# High-Speed_Interfaces.net
KiCad netlist of a schematic drawn in Altium Designer
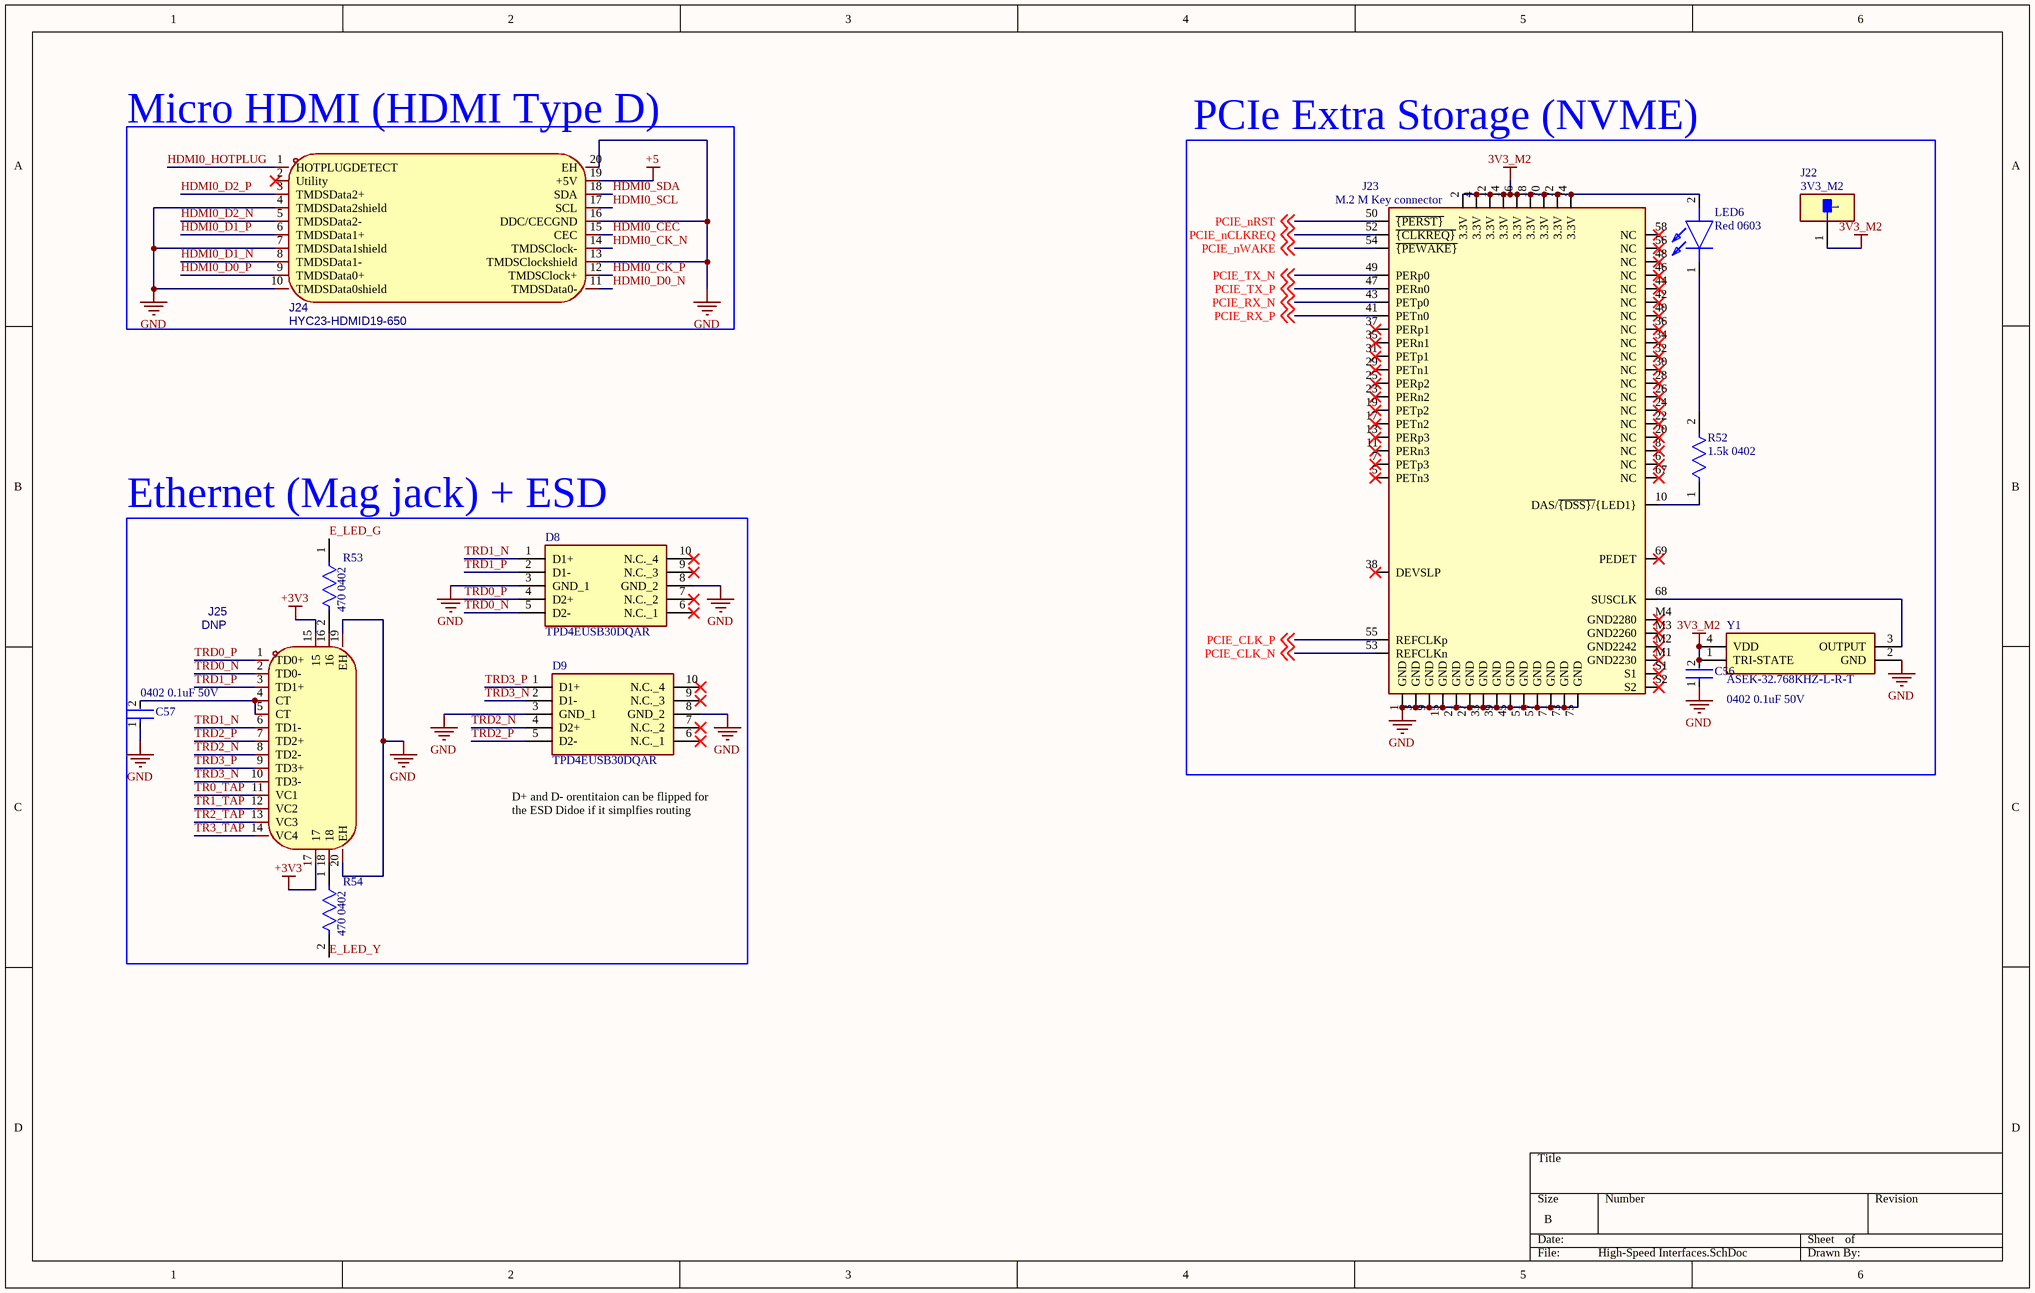
[diagram p0: High-Speed Interfaces.SchDoc]

(export (version "E")
  (design (tool "Eeschema 10.0.6"))
  (components
    (comp (ref "C56")
      (value "0402 0.1uF 50V")
      (footprint "FP-C0402-BB-MFG")
      (description "C307331")
      (fields
        (field (name "TOLERANCE") "0.2")
        (field (name "OCTOPART") "https://octopart.com/c0402c104m3pac7867-kemet-84304880")
      )
      (libsource (lib "Altium Content Vault") (part "b4654b650e69147ec39a6b967a45e02"))
    )
    (comp (ref "C57")
      (value "0402 0.1uF 50V")
      (footprint "FP-C0402-BB-MFG")
      (description "C307331")
      (fields
        (field (name "TOLERANCE") "0.2")
        (field (name "OCTOPART") "https://octopart.com/c0402c104m3pac7867-kemet-84304880")
      )
      (libsource (lib "Altium Content Vault") (part "b4654b650e69147ec39a6b967a45e02"))
    )
    (comp (ref "D8")
      (value "TPD4EUSB30DQAR")
      (footprint "SamacSys:DQA(R-PUSON-N10)")
      (description "C90627")
      (fields (field (name "MOUSER PART NUMBER") "595-TPD4EUSB30DQAR"))
      (libsource (lib "*") (part "TPD4EUSB30DQAR"))
    )
    (comp (ref "D9")
      (value "TPD4EUSB30DQAR")
      (footprint "SamacSys:DQA(R-PUSON-N10)")
      (description "C90627")
      (fields (field (name "MOUSER PART NUMBER") "595-TPD4EUSB30DQAR"))
      (libsource (lib "*") (part "TPD4EUSB30DQAR"))
    )
    (comp (ref "J22")
      (value "3V3_M2")
      (footprint "FP-5015-MFG")
      (description "PC TEST POINT MINIATURE")
      (fields (field (name "MANUFACTURER PART NUMBER") "5015") (field (name "MANUFACTURER") "keystone"))
      (libsource (lib "Altium Content Vault") (part "dd45045ce8184df9e99e12baf3f412c"))
    )
    (comp (ref "J23")
      (value "M.2 M Key connector")
      (footprint "M.2 M Key connector RPI")
      (description "C841661")
      (libsource (lib "Schlib1") (part "M.2 M Key connector RPI"))
    )
    (comp (ref "J24")
      (value "HYC23-HDMID19-650")
      (footprint "AUDIO-TH_HYC23-HDMID19-650")
      (description "C711358")
      (fields (field (name "MANUFACTURER") "华宇创"))
      (libsource (lib "Schlib1") (part "HDMI"))
    )
    (comp (ref "J25")
      (value "DNP")
      (footprint "RJ45-TH_LPJG0926HENL_C22457393")
      (description "C22457393")
      (fields (field (name "MANUFACTURER") "LINK-PP(连普科技)") (field (name "MANUFACTURER PART") "LPJG0926HENL"))
      (libsource (lib "Schlib1") (part "Ethernet Correct"))
    )
    (comp (ref "LED6")
      (value "Red 0603")
      (footprint "SamacSys:LEDC1608X70N")
      (description "C2286")
      (fields (field (name "MANUFACTURER_PART_NUMBER") "KT-0603R"))
      (libsource (lib "*") (part "KT-0603R"))
    )
    (comp (ref "R52")
      (value "1.5k 0402")
      (footprint "FP-AF0402-IPC_B")
      (description "C25867")
      (fields (field (name "TOLERANCE") "5%"))
      (libsource (lib "Altium Content Vault") (part "1029c3af85768c4190bb7ad29bc67b5"))
    )
    (comp (ref "R53")
      (value "470 0402")
      (footprint "FP-RMCF0402-MFG")
      (description "C25117")
      (fields (field (name "TOLERANCE") "5%"))
      (libsource (lib "Altium Content Vault") (part "1029c3af85768c4190bb7ad29bc67b5"))
    )
    (comp (ref "R54")
      (value "470 0402")
      (footprint "FP-RMCF0402-MFG")
      (description "C25117")
      (fields (field (name "TOLERANCE") "5%"))
      (libsource (lib "Altium Content Vault") (part "1029c3af85768c4190bb7ad29bc67b5"))
    )
    (comp (ref "Y1")
      (value "ASEK-32.768KHZ-L-R-T")
      (footprint "SamacSys:ASEK32768KHZLRT")
      (description "C2650753")
      (libsource (lib "*") (part "ASEK-32.768KHZ-L-R-T"))
    )
  )
  (nets
    (net (code "1") (name "+3V3") (class "Default")
      (node (ref "J25") (pin "15") (pinfunction "15_15") (pintype "passive"))
      (node (ref "J25") (pin "17") (pinfunction "17_17") (pintype "passive"))
    )
    (net (code "2") (name "+5") (class "Default")
      (node (ref "J24") (pin "19") (pinfunction "+5V_19") (pintype "passive"))
    )
    (net (code "3") (name "/E_LED_G") (class "Default")
      (node (ref "R53") (pin "1") (pinfunction "1_1") (pintype "passive"))
    )
    (net (code "4") (name "/E_LED_Y") (class "Default")
      (node (ref "R54") (pin "2") (pinfunction "2_2") (pintype "passive"))
    )
    (net (code "5") (name "/HDMI0_CEC") (class "Default")
      (node (ref "J24") (pin "15") (pinfunction "CEC_15") (pintype "passive"))
    )
    (net (code "6") (name "/HDMI0_CK_N") (class "Default")
      (node (ref "J24") (pin "14") (pinfunction "TMDSClock-_14") (pintype "passive"))
    )
    (net (code "7") (name "/HDMI0_CK_P") (class "Default")
      (node (ref "J24") (pin "12") (pinfunction "TMDSClock+_12") (pintype "passive"))
    )
    (net (code "8") (name "/HDMI0_D0_N") (class "Default")
      (node (ref "J24") (pin "11") (pinfunction "TMDSData0-_11") (pintype "passive"))
    )
    (net (code "9") (name "/HDMI0_D0_P") (class "Default")
      (node (ref "J24") (pin "9") (pinfunction "TMDSData0+_9") (pintype "passive"))
    )
    (net (code "10") (name "/HDMI0_D1_N") (class "Default")
      (node (ref "J24") (pin "8") (pinfunction "TMDSData1-_8") (pintype "passive"))
    )
    (net (code "11") (name "/HDMI0_D1_P") (class "Default")
      (node (ref "J24") (pin "6") (pinfunction "TMDSData1+_6") (pintype "passive"))
    )
    (net (code "12") (name "/HDMI0_D2_N") (class "Default")
      (node (ref "J24") (pin "5") (pinfunction "TMDSData2-_5") (pintype "passive"))
    )
    (net (code "13") (name "/HDMI0_D2_P") (class "Default")
      (node (ref "J24") (pin "3") (pinfunction "TMDSData2+_3") (pintype "passive"))
    )
    (net (code "14") (name "/HDMI0_HOTPLUG") (class "Default")
      (node (ref "J24") (pin "1") (pinfunction "HOTPLUGDETECT_1") (pintype "passive"))
    )
    (net (code "15") (name "/HDMI0_SCL") (class "Default")
      (node (ref "J24") (pin "17") (pinfunction "SCL_17") (pintype "passive"))
    )
    (net (code "16") (name "/HDMI0_SDA") (class "Default")
      (node (ref "J24") (pin "18") (pinfunction "SDA_18") (pintype "passive"))
    )
    (net (code "17") (name "/TR0_TAP") (class "Default")
      (node (ref "J25") (pin "11") (pinfunction "VC1_11") (pintype "passive"))
    )
    (net (code "18") (name "/TR1_TAP") (class "Default")
      (node (ref "J25") (pin "12") (pinfunction "VC2_12") (pintype "passive"))
    )
    (net (code "19") (name "/TR2_TAP") (class "Default")
      (node (ref "J25") (pin "13") (pinfunction "VC3_13") (pintype "passive"))
    )
    (net (code "20") (name "/TR3_TAP") (class "Default")
      (node (ref "J25") (pin "14") (pinfunction "VC4_14") (pintype "passive"))
    )
    (net (code "21") (name "/TRD0_N") (class "Default")
      (node (ref "D8") (pin "5") (pinfunction "D2-_5") (pintype "passive"))
      (node (ref "J25") (pin "2") (pinfunction "TD0-_2") (pintype "passive"))
    )
    (net (code "22") (name "/TRD0_P") (class "Default")
      (node (ref "D8") (pin "4") (pinfunction "D2+_4") (pintype "passive"))
      (node (ref "J25") (pin "1") (pinfunction "TD0+_1") (pintype "passive"))
    )
    (net (code "23") (name "/TRD1_N") (class "Default")
      (node (ref "D8") (pin "1") (pinfunction "D1+_1") (pintype "passive"))
      (node (ref "J25") (pin "6") (pinfunction "TD1-_6") (pintype "passive"))
    )
    (net (code "24") (name "/TRD1_P") (class "Default")
      (node (ref "D8") (pin "2") (pinfunction "D1-_2") (pintype "passive"))
      (node (ref "J25") (pin "3") (pinfunction "TD1+_3") (pintype "passive"))
    )
    (net (code "25") (name "/TRD2_N") (class "Default")
      (node (ref "D9") (pin "4") (pinfunction "D2+_4") (pintype "passive"))
      (node (ref "J25") (pin "8") (pinfunction "TD2-_8") (pintype "passive"))
    )
    (net (code "26") (name "/TRD2_P") (class "Default")
      (node (ref "D9") (pin "5") (pinfunction "D2-_5") (pintype "passive"))
      (node (ref "J25") (pin "7") (pinfunction "TD2+_7") (pintype "passive"))
    )
    (net (code "27") (name "/TRD3_N") (class "Default")
      (node (ref "D9") (pin "2") (pinfunction "D1-_2") (pintype "passive"))
      (node (ref "J25") (pin "10") (pinfunction "TD3-_10") (pintype "passive"))
    )
    (net (code "28") (name "/TRD3_P") (class "Default")
      (node (ref "D9") (pin "1") (pinfunction "D1+_1") (pintype "passive"))
      (node (ref "J25") (pin "9") (pinfunction "TD3+_9") (pintype "passive"))
    )
    (net (code "29") (name "3V3_M2") (class "Default")
      (node (ref "C56") (pin "2") (pinfunction "2_2") (pintype "passive"))
      (node (ref "J22") (pin "1") (pinfunction "1_1") (pintype "passive"))
      (node (ref "J23") (pin "12") (pinfunction "3.3V_12") (pintype "passive"))
      (node (ref "J23") (pin "14") (pinfunction "3.3V_14") (pintype "passive"))
      (node (ref "J23") (pin "16") (pinfunction "3.3V_16") (pintype "passive"))
      (node (ref "J23") (pin "18") (pinfunction "3.3V_18") (pintype "passive"))
      (node (ref "J23") (pin "2") (pinfunction "3.3V_2") (pintype "passive"))
      (node (ref "J23") (pin "4") (pinfunction "3.3V_4") (pintype "passive"))
      (node (ref "J23") (pin "70") (pinfunction "3.3V_70") (pintype "passive"))
      (node (ref "J23") (pin "72") (pinfunction "3.3V_72") (pintype "passive"))
      (node (ref "J23") (pin "74") (pinfunction "3.3V_74") (pintype "passive"))
      (node (ref "LED6") (pin "2") (pinfunction "A_2") (pintype "passive"))
      (node (ref "Y1") (pin "1") (pinfunction "TRI-STATE_1") (pintype "passive"))
      (node (ref "Y1") (pin "4") (pinfunction "VDD_4") (pintype "passive"))
    )
    (net (code "30") (name "GND") (class "Default")
      (node (ref "C56") (pin "1") (pinfunction "1_1") (pintype "passive"))
      (node (ref "C57") (pin "1") (pinfunction "1_1") (pintype "passive"))
      (node (ref "D8") (pin "3") (pinfunction "GND_1_3") (pintype "passive"))
      (node (ref "D8") (pin "8") (pinfunction "GND_2_8") (pintype "passive"))
      (node (ref "D9") (pin "3") (pinfunction "GND_1_3") (pintype "passive"))
      (node (ref "D9") (pin "8") (pinfunction "GND_2_8") (pintype "passive"))
      (node (ref "J23") (pin "1") (pinfunction "GND_1") (pintype "passive"))
      (node (ref "J23") (pin "15") (pinfunction "GND_15") (pintype "passive"))
      (node (ref "J23") (pin "21") (pinfunction "GND_21") (pintype "passive"))
      (node (ref "J23") (pin "27") (pinfunction "GND_27") (pintype "passive"))
      (node (ref "J23") (pin "3") (pinfunction "GND_3") (pintype "passive"))
      (node (ref "J23") (pin "33") (pinfunction "GND_33") (pintype "passive"))
      (node (ref "J23") (pin "39") (pinfunction "GND_39") (pintype "passive"))
      (node (ref "J23") (pin "45") (pinfunction "GND_45") (pintype "passive"))
      (node (ref "J23") (pin "51") (pinfunction "GND_51") (pintype "passive"))
      (node (ref "J23") (pin "57") (pinfunction "GND_57") (pintype "passive"))
      (node (ref "J23") (pin "71") (pinfunction "GND_71") (pintype "passive"))
      (node (ref "J23") (pin "73") (pinfunction "GND_73") (pintype "passive"))
      (node (ref "J23") (pin "75") (pinfunction "GND_75") (pintype "passive"))
      (node (ref "J23") (pin "9") (pinfunction "GND_9") (pintype "passive"))
      (node (ref "J24") (pin "10") (pinfunction "TMDSData0shield_10") (pintype "passive"))
      (node (ref "J24") (pin "13") (pinfunction "TMDSClockshield_13") (pintype "passive"))
      (node (ref "J24") (pin "16") (pinfunction "DDC/CECGND_16") (pintype "passive"))
      (node (ref "J24") (pin "20") (pinfunction "EH_20") (pintype "passive"))
      (node (ref "J24") (pin "4") (pinfunction "TMDSData2shield_4") (pintype "passive"))
      (node (ref "J24") (pin "7") (pinfunction "TMDSData1shield_7") (pintype "passive"))
      (node (ref "J25") (pin "19") (pinfunction "EH_19") (pintype "passive"))
      (node (ref "J25") (pin "20") (pinfunction "EH_20") (pintype "passive"))
      (node (ref "Y1") (pin "2") (pinfunction "GND_2") (pintype "passive"))
    )
    (net (code "31") (name "Net-(C57-Pad2)") (class "Default")
      (node (ref "C57") (pin "2") (pinfunction "2_2") (pintype "passive"))
      (node (ref "J25") (pin "4") (pinfunction "CT_4") (pintype "passive"))
      (node (ref "J25") (pin "5") (pinfunction "CT_5") (pintype "passive"))
    )
    (net (code "32") (name "Net-(J23-DAS{slash}~{{DSS}{slash}}{LED1})") (class "Default")
      (node (ref "J23") (pin "10") (pinfunction "DAS/~{{DSS}/}{LED1}_10") (pintype "passive"))
      (node (ref "R52") (pin "1") (pinfunction "1_1") (pintype "passive"))
    )
    (net (code "33") (name "Net-(J23-SUSCLK)") (class "Default")
      (node (ref "J23") (pin "68") (pinfunction "SUSCLK_68") (pintype "passive"))
      (node (ref "Y1") (pin "3") (pinfunction "OUTPUT_3") (pintype "passive"))
    )
    (net (code "34") (name "Net-(J25-Pad16)") (class "Default")
      (node (ref "J25") (pin "16") (pinfunction "16_16") (pintype "passive"))
      (node (ref "R53") (pin "2") (pinfunction "2_2") (pintype "passive"))
    )
    (net (code "35") (name "Net-(J25-Pad18)") (class "Default")
      (node (ref "J25") (pin "18") (pinfunction "18_18") (pintype "passive"))
      (node (ref "R54") (pin "1") (pinfunction "1_1") (pintype "passive"))
    )
    (net (code "36") (name "Net-(LED6-K)") (class "Default")
      (node (ref "LED6") (pin "1") (pinfunction "K_1") (pintype "passive"))
      (node (ref "R52") (pin "2") (pinfunction "2_2") (pintype "passive"))
    )
    (net (code "37") (name "PCIE_CLK_N") (class "Default")
      (node (ref "J23") (pin "53") (pinfunction "REFCLKn_53") (pintype "passive"))
    )
    (net (code "38") (name "PCIE_CLK_P") (class "Default")
      (node (ref "J23") (pin "55") (pinfunction "REFCLKp_55") (pintype "passive"))
    )
    (net (code "39") (name "PCIE_RX_N") (class "Default")
      (node (ref "J23") (pin "43") (pinfunction "PETp0_43") (pintype "passive"))
    )
    (net (code "40") (name "PCIE_RX_P") (class "Default")
      (node (ref "J23") (pin "41") (pinfunction "PETn0_41") (pintype "passive"))
    )
    (net (code "41") (name "PCIE_TX_N") (class "Default")
      (node (ref "J23") (pin "49") (pinfunction "PERp0_49") (pintype "passive"))
    )
    (net (code "42") (name "PCIE_TX_P") (class "Default")
      (node (ref "J23") (pin "47") (pinfunction "PERn0_47") (pintype "passive"))
    )
    (net (code "43") (name "PCIE_nCLKREQ") (class "Default")
      (node (ref "J23") (pin "52") (pinfunction "~{{CLKREQ}}_52") (pintype "passive"))
    )
    (net (code "44") (name "PCIE_nRST") (class "Default")
      (node (ref "J23") (pin "50") (pinfunction "~{{PERST}}_50") (pintype "passive"))
    )
    (net (code "45") (name "PCIE_nWAKE") (class "Default")
      (node (ref "J23") (pin "54") (pinfunction "~{{PEWAKE}}_54") (pintype "passive"))
    )
    (net (code "46") (name "unconnected-(D8-N.C._1-Pad6)") (class "Default")
      (node (ref "D8") (pin "6") (pinfunction "N.C._1_6") (pintype "passive+no_connect"))
    )
    (net (code "47") (name "unconnected-(D8-N.C._2-Pad7)") (class "Default")
      (node (ref "D8") (pin "7") (pinfunction "N.C._2_7") (pintype "passive+no_connect"))
    )
    (net (code "48") (name "unconnected-(D8-N.C._3-Pad9)") (class "Default")
      (node (ref "D8") (pin "9") (pinfunction "N.C._3_9") (pintype "passive+no_connect"))
    )
    (net (code "49") (name "unconnected-(D8-N.C._4-Pad10)") (class "Default")
      (node (ref "D8") (pin "10") (pinfunction "N.C._4_10") (pintype "passive+no_connect"))
    )
    (net (code "50") (name "unconnected-(D9-N.C._1-Pad6)") (class "Default")
      (node (ref "D9") (pin "6") (pinfunction "N.C._1_6") (pintype "passive+no_connect"))
    )
    (net (code "51") (name "unconnected-(D9-N.C._2-Pad7)") (class "Default")
      (node (ref "D9") (pin "7") (pinfunction "N.C._2_7") (pintype "passive+no_connect"))
    )
    (net (code "52") (name "unconnected-(D9-N.C._3-Pad9)") (class "Default")
      (node (ref "D9") (pin "9") (pinfunction "N.C._3_9") (pintype "passive+no_connect"))
    )
    (net (code "53") (name "unconnected-(D9-N.C._4-Pad10)") (class "Default")
      (node (ref "D9") (pin "10") (pinfunction "N.C._4_10") (pintype "passive+no_connect"))
    )
    (net (code "54") (name "unconnected-(J23-DEVSLP-Pad38)") (class "Default")
      (node (ref "J23") (pin "38") (pinfunction "DEVSLP_38") (pintype "passive+no_connect"))
    )
    (net (code "55") (name "unconnected-(J23-GND2230-PadM1)") (class "Default")
      (node (ref "J23") (pin "M1") (pinfunction "GND2230_M1") (pintype "passive+no_connect"))
    )
    (net (code "56") (name "unconnected-(J23-GND2242-PadM2)") (class "Default")
      (node (ref "J23") (pin "M2") (pinfunction "GND2242_M2") (pintype "passive+no_connect"))
    )
    (net (code "57") (name "unconnected-(J23-GND2260-PadM3)") (class "Default")
      (node (ref "J23") (pin "M3") (pinfunction "GND2260_M3") (pintype "passive+no_connect"))
    )
    (net (code "58") (name "unconnected-(J23-GND2280-PadM4)") (class "Default")
      (node (ref "J23") (pin "M4") (pinfunction "GND2280_M4") (pintype "passive+no_connect"))
    )
    (net (code "59") (name "unconnected-(J23-NC-Pad6)") (class "Default")
      (node (ref "J23") (pin "6") (pinfunction "NC_6") (pintype "passive+no_connect"))
    )
    (net (code "60") (name "unconnected-(J23-NC-Pad8)") (class "Default")
      (node (ref "J23") (pin "8") (pinfunction "NC_8") (pintype "passive+no_connect"))
    )
    (net (code "61") (name "unconnected-(J23-NC-Pad20)") (class "Default")
      (node (ref "J23") (pin "20") (pinfunction "NC_20") (pintype "passive+no_connect"))
    )
    (net (code "62") (name "unconnected-(J23-NC-Pad22)") (class "Default")
      (node (ref "J23") (pin "22") (pinfunction "NC_22") (pintype "passive+no_connect"))
    )
    (net (code "63") (name "unconnected-(J23-NC-Pad24)") (class "Default")
      (node (ref "J23") (pin "24") (pinfunction "NC_24") (pintype "passive+no_connect"))
    )
    (net (code "64") (name "unconnected-(J23-NC-Pad26)") (class "Default")
      (node (ref "J23") (pin "26") (pinfunction "NC_26") (pintype "passive+no_connect"))
    )
    (net (code "65") (name "unconnected-(J23-NC-Pad28)") (class "Default")
      (node (ref "J23") (pin "28") (pinfunction "NC_28") (pintype "passive+no_connect"))
    )
    (net (code "66") (name "unconnected-(J23-NC-Pad30)") (class "Default")
      (node (ref "J23") (pin "30") (pinfunction "NC_30") (pintype "passive+no_connect"))
    )
    (net (code "67") (name "unconnected-(J23-NC-Pad32)") (class "Default")
      (node (ref "J23") (pin "32") (pinfunction "NC_32") (pintype "passive+no_connect"))
    )
    (net (code "68") (name "unconnected-(J23-NC-Pad34)") (class "Default")
      (node (ref "J23") (pin "34") (pinfunction "NC_34") (pintype "passive+no_connect"))
    )
    (net (code "69") (name "unconnected-(J23-NC-Pad36)") (class "Default")
      (node (ref "J23") (pin "36") (pinfunction "NC_36") (pintype "passive+no_connect"))
    )
    (net (code "70") (name "unconnected-(J23-NC-Pad40)") (class "Default")
      (node (ref "J23") (pin "40") (pinfunction "NC_40") (pintype "passive+no_connect"))
    )
    (net (code "71") (name "unconnected-(J23-NC-Pad42)") (class "Default")
      (node (ref "J23") (pin "42") (pinfunction "NC_42") (pintype "passive+no_connect"))
    )
    (net (code "72") (name "unconnected-(J23-NC-Pad44)") (class "Default")
      (node (ref "J23") (pin "44") (pinfunction "NC_44") (pintype "passive+no_connect"))
    )
    (net (code "73") (name "unconnected-(J23-NC-Pad46)") (class "Default")
      (node (ref "J23") (pin "46") (pinfunction "NC_46") (pintype "passive+no_connect"))
    )
    (net (code "74") (name "unconnected-(J23-NC-Pad48)") (class "Default")
      (node (ref "J23") (pin "48") (pinfunction "NC_48") (pintype "passive+no_connect"))
    )
    (net (code "75") (name "unconnected-(J23-NC-Pad56)") (class "Default")
      (node (ref "J23") (pin "56") (pinfunction "NC_56") (pintype "passive+no_connect"))
    )
    (net (code "76") (name "unconnected-(J23-NC-Pad58)") (class "Default")
      (node (ref "J23") (pin "58") (pinfunction "NC_58") (pintype "passive+no_connect"))
    )
    (net (code "77") (name "unconnected-(J23-NC-Pad67)") (class "Default")
      (node (ref "J23") (pin "67") (pinfunction "NC_67") (pintype "passive+no_connect"))
    )
    (net (code "78") (name "unconnected-(J23-PEDET-Pad69)") (class "Default")
      (node (ref "J23") (pin "69") (pinfunction "PEDET_69") (pintype "passive+no_connect"))
    )
    (net (code "79") (name "unconnected-(J23-PERn1-Pad35)") (class "Default")
      (node (ref "J23") (pin "35") (pinfunction "PERn1_35") (pintype "passive+no_connect"))
    )
    (net (code "80") (name "unconnected-(J23-PERn2-Pad23)") (class "Default")
      (node (ref "J23") (pin "23") (pinfunction "PERn2_23") (pintype "passive+no_connect"))
    )
    (net (code "81") (name "unconnected-(J23-PERn3-Pad11)") (class "Default")
      (node (ref "J23") (pin "11") (pinfunction "PERn3_11") (pintype "passive+no_connect"))
    )
    (net (code "82") (name "unconnected-(J23-PERp1-Pad37)") (class "Default")
      (node (ref "J23") (pin "37") (pinfunction "PERp1_37") (pintype "passive+no_connect"))
    )
    (net (code "83") (name "unconnected-(J23-PERp2-Pad25)") (class "Default")
      (node (ref "J23") (pin "25") (pinfunction "PERp2_25") (pintype "passive+no_connect"))
    )
    (net (code "84") (name "unconnected-(J23-PERp3-Pad13)") (class "Default")
      (node (ref "J23") (pin "13") (pinfunction "PERp3_13") (pintype "passive+no_connect"))
    )
    (net (code "85") (name "unconnected-(J23-PETn1-Pad29)") (class "Default")
      (node (ref "J23") (pin "29") (pinfunction "PETn1_29") (pintype "passive+no_connect"))
    )
    (net (code "86") (name "unconnected-(J23-PETn2-Pad17)") (class "Default")
      (node (ref "J23") (pin "17") (pinfunction "PETn2_17") (pintype "passive+no_connect"))
    )
    (net (code "87") (name "unconnected-(J23-PETn3-Pad5)") (class "Default")
      (node (ref "J23") (pin "5") (pinfunction "PETn3_5") (pintype "passive+no_connect"))
    )
    (net (code "88") (name "unconnected-(J23-PETp1-Pad31)") (class "Default")
      (node (ref "J23") (pin "31") (pinfunction "PETp1_31") (pintype "passive+no_connect"))
    )
    (net (code "89") (name "unconnected-(J23-PETp2-Pad19)") (class "Default")
      (node (ref "J23") (pin "19") (pinfunction "PETp2_19") (pintype "passive+no_connect"))
    )
    (net (code "90") (name "unconnected-(J23-PETp3-Pad7)") (class "Default")
      (node (ref "J23") (pin "7") (pinfunction "PETp3_7") (pintype "passive+no_connect"))
    )
    (net (code "91") (name "unconnected-(J23-PadS1)") (class "Default")
      (node (ref "J23") (pin "S1") (pinfunction "S1_S1") (pintype "passive+no_connect"))
    )
    (net (code "92") (name "unconnected-(J23-PadS2)") (class "Default")
      (node (ref "J23") (pin "S2") (pinfunction "S2_S2") (pintype "passive+no_connect"))
    )
    (net (code "93") (name "unconnected-(J24-Utility-Pad2)") (class "Default")
      (node (ref "J24") (pin "2") (pinfunction "Utility_2") (pintype "passive+no_connect"))
    )
  )
)
